# Main_schem.net
KiCad netlist of a schematic drawn in Altium Designer
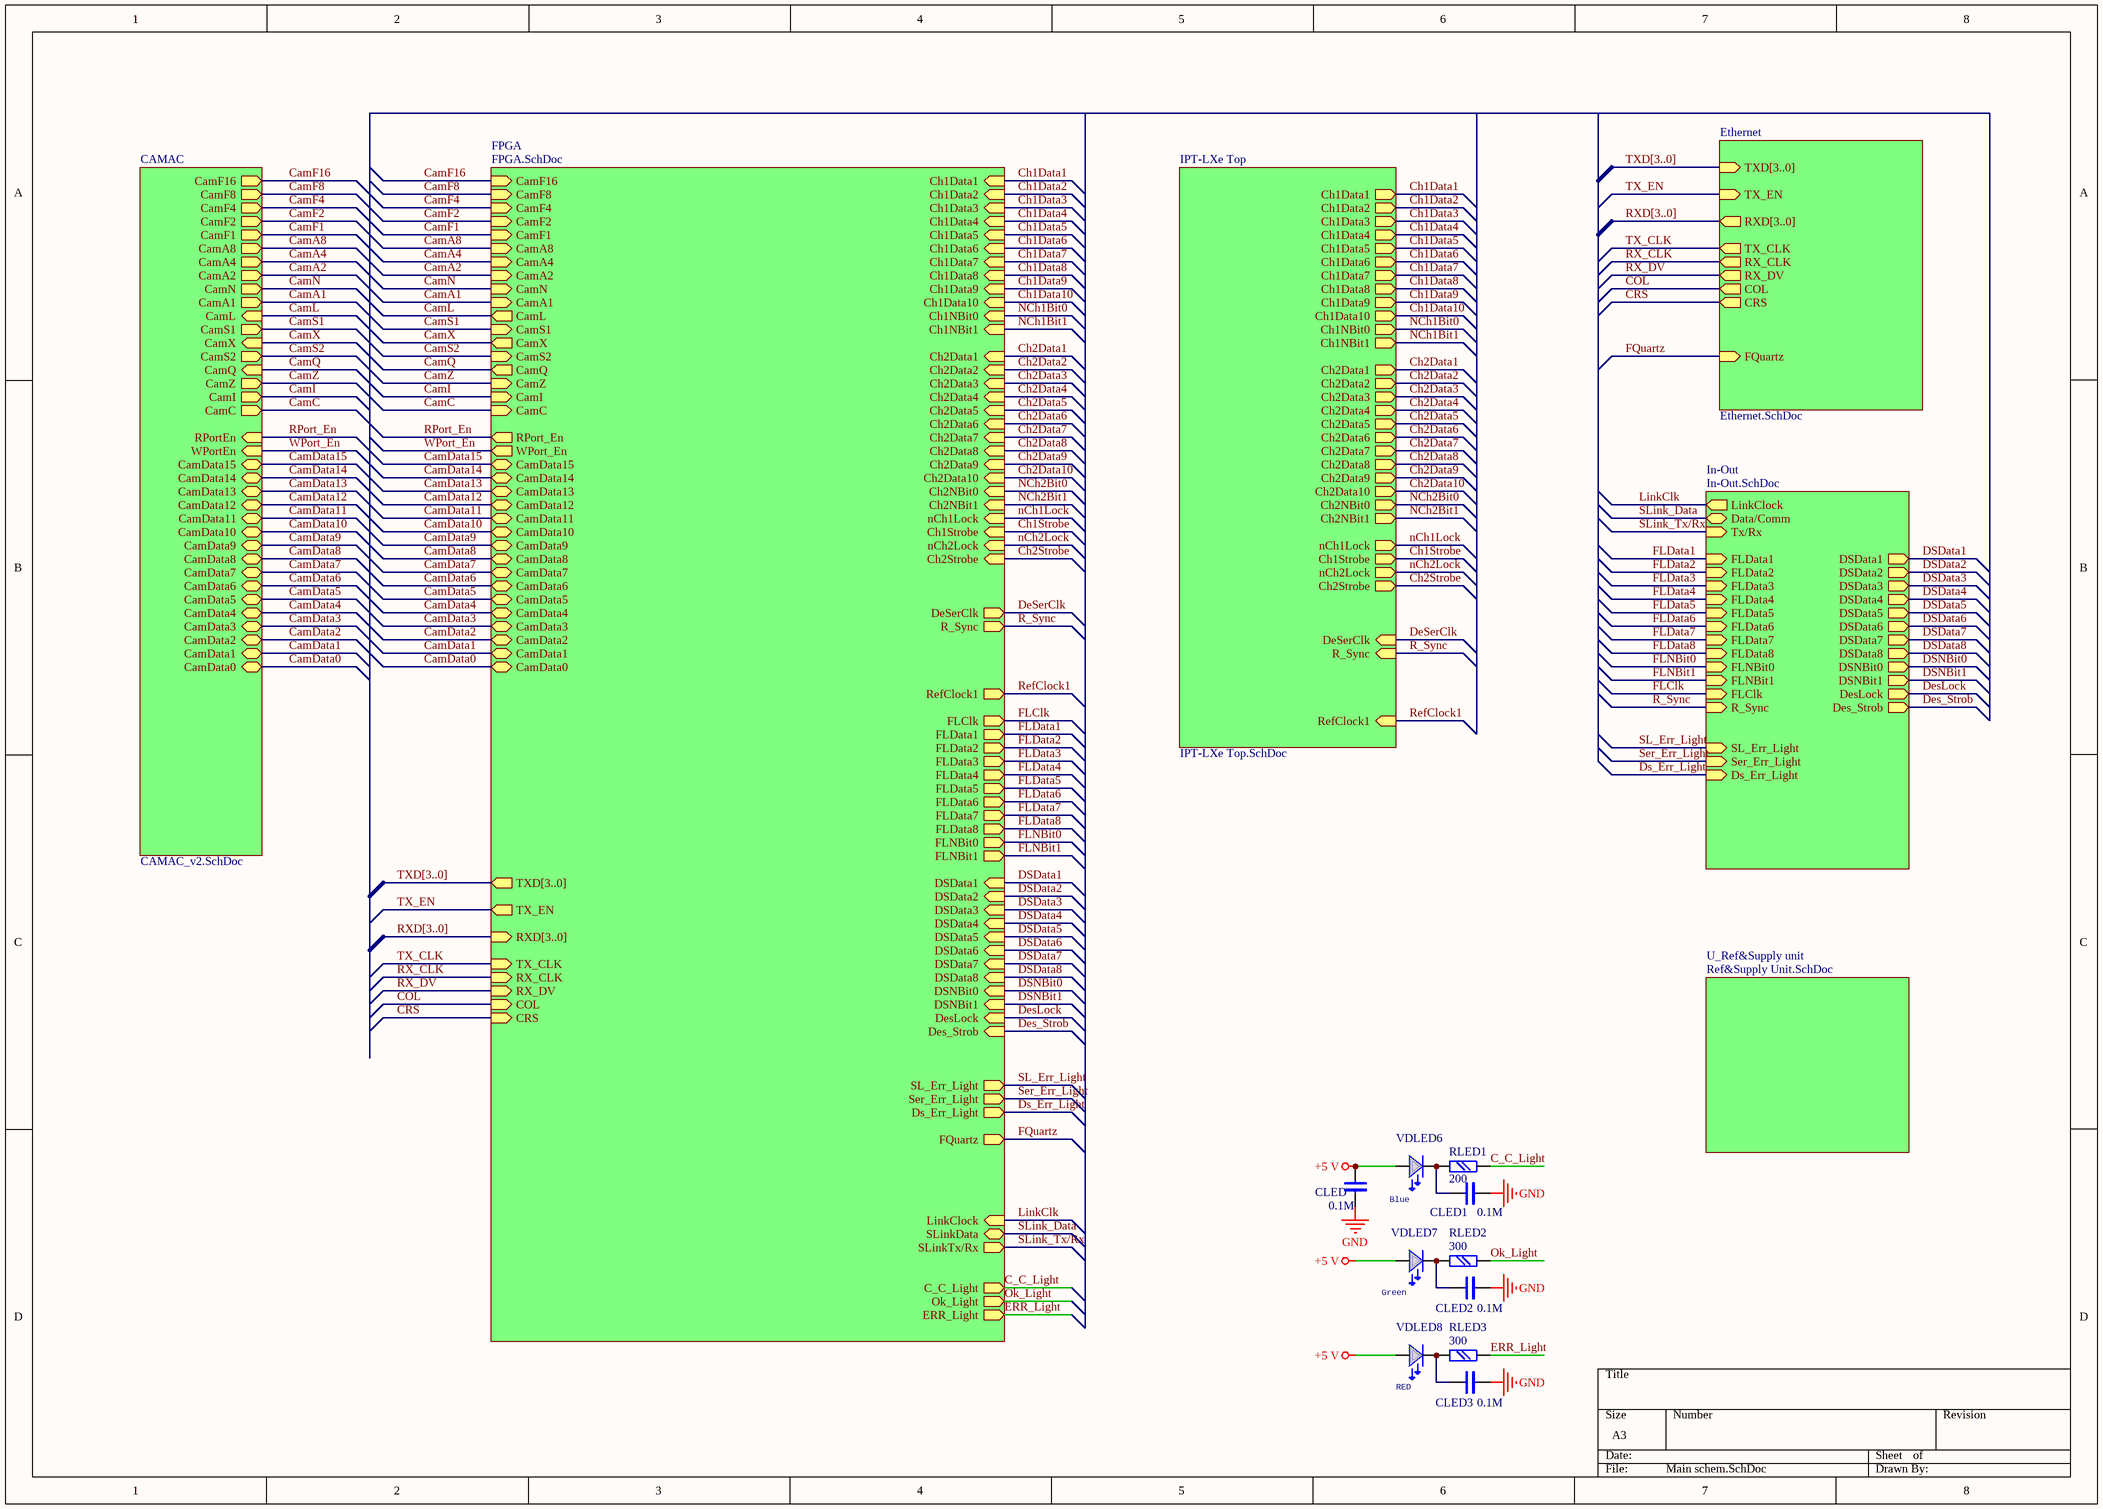
[diagram p0: Main schem.SchDoc]

(export (version "E")
  (design (tool "Eeschema 10.0.6"))
  (components
    (comp (ref "CLED") (value "0.1M") (footprint "chip0805") (libsource (lib "*") (part "C")))
    (comp (ref "CLED1") (value "0.1M") (footprint "chip0805") (libsource (lib "*") (part "C")))
    (comp (ref "CLED2") (value "0.1M") (footprint "chip0805") (libsource (lib "*") (part "C")))
    (comp (ref "CLED3") (value "0.1M") (footprint "chip0805") (libsource (lib "*") (part "C")))
    (comp (ref "RLED1") (value "200") (footprint "chip0805") (libsource (lib "*") (part "R")))
    (comp (ref "RLED2") (value "300") (footprint "chip0805") (libsource (lib "*") (part "R")))
    (comp (ref "RLED3") (value "300") (footprint "chip0805") (libsource (lib "*") (part "R")))
    (comp (ref "VDLED6") (value "LED") (footprint "LED2P5_H") (libsource (lib "*") (part "AL307")))
    (comp (ref "VDLED7") (value "LED") (footprint "LED2P5_H") (libsource (lib "*") (part "AL307")))
    (comp (ref "VDLED8") (value "LED") (footprint "LED2P5_H") (libsource (lib "*") (part "AL307")))
  )
  (nets
    (net (code "9") (name "+5 V") (class "Default")
      (node (ref "CLED") (pin "1") (pinfunction "1_1") (pintype "passive"))
      (node (ref "VDLED6") (pin "ANOD") (pinfunction "ANOD_ANOD") (pintype "passive"))
      (node (ref "VDLED7") (pin "ANOD") (pinfunction "ANOD_ANOD") (pintype "passive"))
      (node (ref "VDLED8") (pin "ANOD") (pinfunction "ANOD_ANOD") (pintype "passive"))
    )
    (net (code "12") (name "/C_C_Light") (class "Default")
      (node (ref "RLED1") (pin "2") (pinfunction "2_2") (pintype "passive"))
    )
    (net (code "83") (name "/ERR_Light") (class "Default")
      (node (ref "RLED3") (pin "2") (pinfunction "2_2") (pintype "passive"))
    )
    (net (code "101") (name "/Ok_Light") (class "Default")
      (node (ref "RLED2") (pin "2") (pinfunction "2_2") (pintype "passive"))
    )
    (net (code "118") (name "GND") (class "Default")
      (node (ref "CLED") (pin "2") (pinfunction "2_2") (pintype "passive"))
      (node (ref "CLED1") (pin "2") (pinfunction "2_2") (pintype "passive"))
      (node (ref "CLED2") (pin "2") (pinfunction "2_2") (pintype "passive"))
      (node (ref "CLED3") (pin "2") (pinfunction "2_2") (pintype "passive"))
    )
    (net (code "119") (name "Net-(CLED1-Pad1)") (class "Default")
      (node (ref "CLED1") (pin "1") (pinfunction "1_1") (pintype "passive"))
      (node (ref "RLED1") (pin "1") (pinfunction "1_1") (pintype "passive"))
      (node (ref "VDLED6") (pin "CATH") (pinfunction "CATH_CATH") (pintype "passive"))
    )
    (net (code "120") (name "Net-(CLED2-Pad1)") (class "Default")
      (node (ref "CLED2") (pin "1") (pinfunction "1_1") (pintype "passive"))
      (node (ref "RLED2") (pin "1") (pinfunction "1_1") (pintype "passive"))
      (node (ref "VDLED7") (pin "CATH") (pinfunction "CATH_CATH") (pintype "passive"))
    )
    (net (code "121") (name "Net-(CLED3-Pad1)") (class "Default")
      (node (ref "CLED3") (pin "1") (pinfunction "1_1") (pintype "passive"))
      (node (ref "RLED3") (pin "1") (pinfunction "1_1") (pintype "passive"))
      (node (ref "VDLED8") (pin "CATH") (pinfunction "CATH_CATH") (pintype "passive"))
    )
  )
)
